# untitled.net
KiCad netlist of a schematic drawn in EAGLE
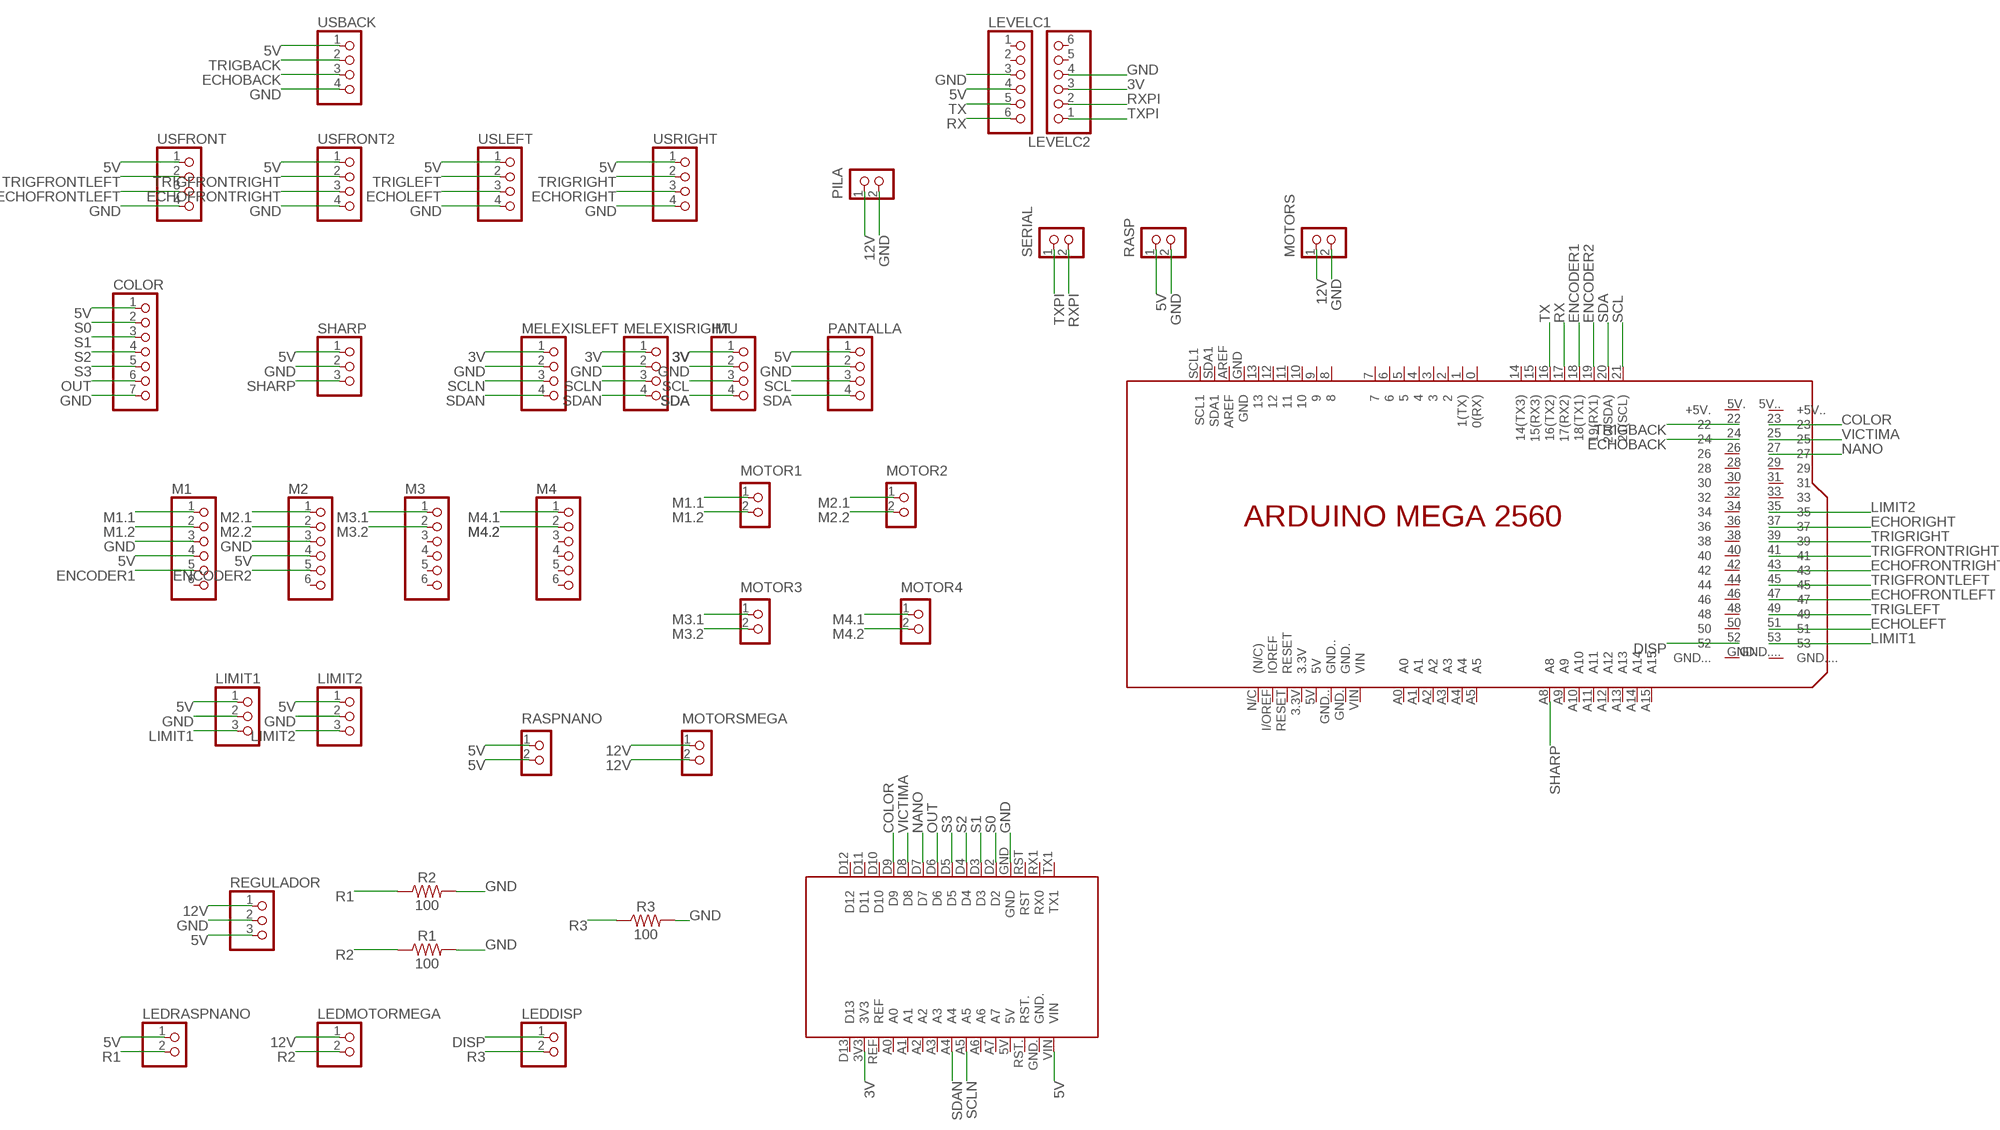
[diagram p0: schematic, sheet 1]

(export (version "E")
  (design (tool "Eeschema 10.0.6"))
  (components
    (comp (ref "COLOR")
      (value "PINHD-1X7")
      (footprint "eagle-import:1X07")
      (libsource (lib "eagle-import") (part "PINHD-1X7"))
    )
    (comp (ref "IMU")
      (value "PINHD-1X4")
      (footprint "eagle-import:1X04")
      (libsource (lib "eagle-import") (part "PINHD-1X4"))
    )
    (comp (ref "LEDDISP")
      (value "PINHD-1X2")
      (footprint "eagle-import:1X02")
      (libsource (lib "eagle-import") (part "PINHD-1X2"))
    )
    (comp (ref "LEDMOTORMEGA")
      (value "PINHD-1X2")
      (footprint "eagle-import:1X02")
      (libsource (lib "eagle-import") (part "PINHD-1X2"))
    )
    (comp (ref "LEDRASPNANO")
      (value "PINHD-1X2")
      (footprint "eagle-import:1X02")
      (libsource (lib "eagle-import") (part "PINHD-1X2"))
    )
    (comp (ref "LEVELC1")
      (value "PINHD-1X6")
      (footprint "eagle-import:1X06")
      (libsource (lib "eagle-import") (part "PINHD-1X6"))
    )
    (comp (ref "LEVELC2")
      (value "PINHD-1X6")
      (footprint "eagle-import:1X06")
      (libsource (lib "eagle-import") (part "PINHD-1X6"))
    )
    (comp (ref "LIMIT1")
      (value "PINHD-1X3")
      (footprint "eagle-import:1X03")
      (libsource (lib "eagle-import") (part "PINHD-1X3"))
    )
    (comp (ref "LIMIT2")
      (value "PINHD-1X3")
      (footprint "eagle-import:1X03")
      (libsource (lib "eagle-import") (part "PINHD-1X3"))
    )
    (comp (ref "M1")
      (value "PINHD-1X6")
      (footprint "eagle-import:1X06")
      (libsource (lib "eagle-import") (part "PINHD-1X6"))
    )
    (comp (ref "M2")
      (value "PINHD-1X6")
      (footprint "eagle-import:1X06")
      (libsource (lib "eagle-import") (part "PINHD-1X6"))
    )
    (comp (ref "M3")
      (value "PINHD-1X6")
      (footprint "eagle-import:1X06")
      (libsource (lib "eagle-import") (part "PINHD-1X6"))
    )
    (comp (ref "M4")
      (value "PINHD-1X6")
      (footprint "eagle-import:1X06")
      (libsource (lib "eagle-import") (part "PINHD-1X6"))
    )
    (comp (ref "MEGA1")
      (value "MEGA")
      (footprint "eagle-import:MEGA")
      (libsource (lib "eagle-import") (part "MEGA"))
    )
    (comp (ref "MELEXISLEFT")
      (value "PINHD-1X4")
      (footprint "eagle-import:1X04")
      (libsource (lib "eagle-import") (part "PINHD-1X4"))
    )
    (comp (ref "MELEXISRIGHT")
      (value "PINHD-1X4")
      (footprint "eagle-import:1X04")
      (libsource (lib "eagle-import") (part "PINHD-1X4"))
    )
    (comp (ref "MOTOR1")
      (value "CON_TERMINAL_BLOCK_02-5MM")
      (footprint "eagle-import:TERMINAL_BLOCK_2P_5")
      (libsource (lib "eagle-import") (part "CON_TERMINAL_BLOCK_02-5MM"))
    )
    (comp (ref "MOTOR2")
      (value "CON_TERMINAL_BLOCK_02-5MM")
      (footprint "eagle-import:TERMINAL_BLOCK_2P_5")
      (libsource (lib "eagle-import") (part "CON_TERMINAL_BLOCK_02-5MM"))
    )
    (comp (ref "MOTOR3")
      (value "CON_TERMINAL_BLOCK_02-5MM")
      (footprint "eagle-import:TERMINAL_BLOCK_2P_5")
      (libsource (lib "eagle-import") (part "CON_TERMINAL_BLOCK_02-5MM"))
    )
    (comp (ref "MOTOR4")
      (value "CON_TERMINAL_BLOCK_02-5MM")
      (footprint "eagle-import:TERMINAL_BLOCK_2P_5")
      (libsource (lib "eagle-import") (part "CON_TERMINAL_BLOCK_02-5MM"))
    )
    (comp (ref "MOTORS")
      (value "CON_TERMINAL_BLOCK_02-5MM")
      (footprint "eagle-import:TERMINAL_BLOCK_2P_5")
      (libsource (lib "eagle-import") (part "CON_TERMINAL_BLOCK_02-5MM"))
    )
    (comp (ref "MOTORSMEGA")
      (value "CON_TERMINAL_BLOCK_02-5MM")
      (footprint "eagle-import:TERMINAL_BLOCK_2P_5")
      (libsource (lib "eagle-import") (part "CON_TERMINAL_BLOCK_02-5MM"))
    )
    (comp (ref "PANTALLA")
      (value "PINHD-1X4")
      (footprint "eagle-import:1X04")
      (libsource (lib "eagle-import") (part "PINHD-1X4"))
    )
    (comp (ref "PILA")
      (value "CON_TERMINAL_BLOCK_02-5MM")
      (footprint "eagle-import:TERMINAL_BLOCK_2P_5")
      (libsource (lib "eagle-import") (part "CON_TERMINAL_BLOCK_02-5MM"))
    )
    (comp (ref "R1")
      (value "100")
      (footprint "eagle-import:AXIAL-0.3EZ")
      (libsource (lib "eagle-import") (part "100OHM-HORIZ_KIT-1/4W-1%"))
    )
    (comp (ref "R2")
      (value "100")
      (footprint "eagle-import:AXIAL-0.3EZ")
      (libsource (lib "eagle-import") (part "100OHM-HORIZ_KIT-1/4W-1%"))
    )
    (comp (ref "R3")
      (value "100")
      (footprint "eagle-import:AXIAL-0.3EZ")
      (libsource (lib "eagle-import") (part "100OHM-HORIZ_KIT-1/4W-1%"))
    )
    (comp (ref "RASP")
      (value "CON_TERMINAL_BLOCK_02-5MM")
      (footprint "eagle-import:TERMINAL_BLOCK_2P_5")
      (libsource (lib "eagle-import") (part "CON_TERMINAL_BLOCK_02-5MM"))
    )
    (comp (ref "RASPNANO")
      (value "CON_TERMINAL_BLOCK_02-5MM")
      (footprint "eagle-import:TERMINAL_BLOCK_2P_5")
      (libsource (lib "eagle-import") (part "CON_TERMINAL_BLOCK_02-5MM"))
    )
    (comp (ref "REGULADOR")
      (value "PINHD-1X3")
      (footprint "eagle-import:1X03")
      (libsource (lib "eagle-import") (part "PINHD-1X3"))
    )
    (comp (ref "SERIAL")
      (value "CON_TERMINAL_BLOCK_02-5MM")
      (footprint "eagle-import:TERMINAL_BLOCK_2P_5")
      (libsource (lib "eagle-import") (part "CON_TERMINAL_BLOCK_02-5MM"))
    )
    (comp (ref "SHARP")
      (value "PINHD-1X3")
      (footprint "eagle-import:1X03")
      (libsource (lib "eagle-import") (part "PINHD-1X3"))
    )
    (comp (ref "U$1")
      (value "NANO")
      (footprint "eagle-import:NANO")
      (libsource (lib "eagle-import") (part "NANO"))
    )
    (comp (ref "USBACK")
      (value "PINHD-1X4")
      (footprint "eagle-import:1X04")
      (libsource (lib "eagle-import") (part "PINHD-1X4"))
    )
    (comp (ref "USFRONT")
      (value "PINHD-1X4")
      (footprint "eagle-import:1X04")
      (libsource (lib "eagle-import") (part "PINHD-1X4"))
    )
    (comp (ref "USFRONT2")
      (value "PINHD-1X4")
      (footprint "eagle-import:1X04")
      (libsource (lib "eagle-import") (part "PINHD-1X4"))
    )
    (comp (ref "USLEFT")
      (value "PINHD-1X4")
      (footprint "eagle-import:1X04")
      (libsource (lib "eagle-import") (part "PINHD-1X4"))
    )
    (comp (ref "USRIGHT")
      (value "PINHD-1X4")
      (footprint "eagle-import:1X04")
      (libsource (lib "eagle-import") (part "PINHD-1X4"))
    )
  )
  (nets
    (net (code "1") (name "/3V") (class "Default")
      (node (ref "IMU") (pin "1") (pinfunction "1_1") (pintype "passive"))
      (node (ref "LEVELC2") (pin "3") (pinfunction "3_3") (pintype "passive"))
      (node (ref "MELEXISLEFT") (pin "1") (pinfunction "1_1") (pintype "passive"))
      (node (ref "MELEXISRIGHT") (pin "1") (pinfunction "1_1") (pintype "passive"))
      (node (ref "U$1") (pin "3V3") (pinfunction "3V3_3V3") (pintype "bidirectional"))
    )
    (net (code "2") (name "/5V") (class "Default")
      (node (ref "COLOR") (pin "1") (pinfunction "1_1") (pintype "passive"))
      (node (ref "LEDRASPNANO") (pin "1") (pinfunction "1_1") (pintype "passive"))
      (node (ref "LEVELC1") (pin "4") (pinfunction "4_4") (pintype "passive"))
      (node (ref "LIMIT1") (pin "1") (pinfunction "1_1") (pintype "passive"))
      (node (ref "LIMIT2") (pin "1") (pinfunction "1_1") (pintype "passive"))
      (node (ref "M1") (pin "4") (pinfunction "4_4") (pintype "passive"))
      (node (ref "M2") (pin "4") (pinfunction "4_4") (pintype "passive"))
      (node (ref "PANTALLA") (pin "1") (pinfunction "1_1") (pintype "passive"))
      (node (ref "RASP") (pin "1") (pinfunction "1_1") (pintype "passive"))
      (node (ref "RASPNANO") (pin "1") (pinfunction "1_1") (pintype "passive"))
      (node (ref "RASPNANO") (pin "2") (pinfunction "2_2") (pintype "passive"))
      (node (ref "REGULADOR") (pin "3") (pinfunction "3_3") (pintype "passive"))
      (node (ref "SHARP") (pin "1") (pinfunction "1_1") (pintype "passive"))
      (node (ref "U$1") (pin "VIN") (pinfunction "VIN_VIN") (pintype "bidirectional"))
      (node (ref "USBACK") (pin "1") (pinfunction "1_1") (pintype "passive"))
      (node (ref "USFRONT") (pin "1") (pinfunction "1_1") (pintype "passive"))
      (node (ref "USFRONT2") (pin "1") (pinfunction "1_1") (pintype "passive"))
      (node (ref "USLEFT") (pin "1") (pinfunction "1_1") (pintype "passive"))
      (node (ref "USRIGHT") (pin "1") (pinfunction "1_1") (pintype "passive"))
    )
    (net (code "3") (name "/12V") (class "Default")
      (node (ref "LEDMOTORMEGA") (pin "1") (pinfunction "1_1") (pintype "passive"))
      (node (ref "MOTORS") (pin "1") (pinfunction "1_1") (pintype "passive"))
      (node (ref "MOTORSMEGA") (pin "1") (pinfunction "1_1") (pintype "passive"))
      (node (ref "MOTORSMEGA") (pin "2") (pinfunction "2_2") (pintype "passive"))
      (node (ref "PILA") (pin "1") (pinfunction "1_1") (pintype "passive"))
      (node (ref "REGULADOR") (pin "1") (pinfunction "1_1") (pintype "passive"))
    )
    (net (code "4") (name "/COLOR") (class "Default")
      (node (ref "MEGA1") (pin "23") (pinfunction "23_23") (pintype "bidirectional"))
      (node (ref "U$1") (pin "D9") (pinfunction "D9_D9") (pintype "bidirectional"))
    )
    (net (code "5") (name "/DISP") (class "Default")
      (node (ref "LEDDISP") (pin "1") (pinfunction "1_1") (pintype "passive"))
      (node (ref "MEGA1") (pin "52") (pinfunction "52_52") (pintype "bidirectional"))
    )
    (net (code "6") (name "/ECHOBACK") (class "Default")
      (node (ref "MEGA1") (pin "24") (pinfunction "24_24") (pintype "bidirectional"))
      (node (ref "USBACK") (pin "3") (pinfunction "3_3") (pintype "passive"))
    )
    (net (code "7") (name "/ECHOFRONTLEFT") (class "Default")
      (node (ref "MEGA1") (pin "47") (pinfunction "47_47") (pintype "bidirectional"))
      (node (ref "USFRONT") (pin "3") (pinfunction "3_3") (pintype "passive"))
    )
    (net (code "8") (name "/ECHOFRONTRIGHT") (class "Default")
      (node (ref "MEGA1") (pin "43") (pinfunction "43_43") (pintype "bidirectional"))
      (node (ref "USFRONT2") (pin "3") (pinfunction "3_3") (pintype "passive"))
    )
    (net (code "9") (name "/ECHOLEFT") (class "Default")
      (node (ref "MEGA1") (pin "51") (pinfunction "51_51") (pintype "bidirectional"))
      (node (ref "USLEFT") (pin "3") (pinfunction "3_3") (pintype "passive"))
    )
    (net (code "10") (name "/ECHORIGHT") (class "Default")
      (node (ref "MEGA1") (pin "37") (pinfunction "37_37") (pintype "bidirectional"))
      (node (ref "USRIGHT") (pin "3") (pinfunction "3_3") (pintype "passive"))
    )
    (net (code "11") (name "/ENCODER1") (class "Default")
      (node (ref "M1") (pin "5") (pinfunction "5_5") (pintype "passive"))
      (node (ref "MEGA1") (pin "18") (pinfunction "18(TX1)_18") (pintype "bidirectional"))
    )
    (net (code "12") (name "/ENCODER2") (class "Default")
      (node (ref "M2") (pin "5") (pinfunction "5_5") (pintype "passive"))
      (node (ref "MEGA1") (pin "19") (pinfunction "19(RX1)_19") (pintype "bidirectional"))
    )
    (net (code "13") (name "/GND") (class "Default")
      (node (ref "COLOR") (pin "7") (pinfunction "7_7") (pintype "passive"))
      (node (ref "IMU") (pin "2") (pinfunction "2_2") (pintype "passive"))
      (node (ref "LEVELC1") (pin "3") (pinfunction "3_3") (pintype "passive"))
      (node (ref "LEVELC2") (pin "4") (pinfunction "4_4") (pintype "passive"))
      (node (ref "LIMIT1") (pin "2") (pinfunction "2_2") (pintype "passive"))
      (node (ref "LIMIT2") (pin "2") (pinfunction "2_2") (pintype "passive"))
      (node (ref "M1") (pin "3") (pinfunction "3_3") (pintype "passive"))
      (node (ref "M2") (pin "3") (pinfunction "3_3") (pintype "passive"))
      (node (ref "MELEXISLEFT") (pin "2") (pinfunction "2_2") (pintype "passive"))
      (node (ref "MELEXISRIGHT") (pin "2") (pinfunction "2_2") (pintype "passive"))
      (node (ref "MOTORS") (pin "2") (pinfunction "2_2") (pintype "passive"))
      (node (ref "PANTALLA") (pin "2") (pinfunction "2_2") (pintype "passive"))
      (node (ref "PILA") (pin "2") (pinfunction "2_2") (pintype "passive"))
      (node (ref "R1") (pin "P$2") (pinfunction "2_P$2") (pintype "passive"))
      (node (ref "R2") (pin "P$2") (pinfunction "2_P$2") (pintype "passive"))
      (node (ref "R3") (pin "P$2") (pinfunction "2_P$2") (pintype "passive"))
      (node (ref "RASP") (pin "2") (pinfunction "2_2") (pintype "passive"))
      (node (ref "REGULADOR") (pin "2") (pinfunction "2_2") (pintype "passive"))
      (node (ref "SHARP") (pin "2") (pinfunction "2_2") (pintype "passive"))
      (node (ref "U$1") (pin "GND") (pinfunction "GND_GND") (pintype "bidirectional"))
      (node (ref "USBACK") (pin "4") (pinfunction "4_4") (pintype "passive"))
      (node (ref "USFRONT") (pin "4") (pinfunction "4_4") (pintype "passive"))
      (node (ref "USFRONT2") (pin "4") (pinfunction "4_4") (pintype "passive"))
      (node (ref "USLEFT") (pin "4") (pinfunction "4_4") (pintype "passive"))
      (node (ref "USRIGHT") (pin "4") (pinfunction "4_4") (pintype "passive"))
    )
    (net (code "14") (name "/LIMIT1") (class "Default")
      (node (ref "LIMIT1") (pin "3") (pinfunction "3_3") (pintype "passive"))
      (node (ref "MEGA1") (pin "53") (pinfunction "53_53") (pintype "bidirectional"))
    )
    (net (code "15") (name "/LIMIT2") (class "Default")
      (node (ref "LIMIT2") (pin "3") (pinfunction "3_3") (pintype "passive"))
      (node (ref "MEGA1") (pin "35") (pinfunction "35_35") (pintype "bidirectional"))
    )
    (net (code "16") (name "/M1.1") (class "Default")
      (node (ref "M1") (pin "1") (pinfunction "1_1") (pintype "passive"))
      (node (ref "MOTOR1") (pin "1") (pinfunction "1_1") (pintype "passive"))
    )
    (net (code "17") (name "/M1.2") (class "Default")
      (node (ref "M1") (pin "2") (pinfunction "2_2") (pintype "passive"))
      (node (ref "MOTOR1") (pin "2") (pinfunction "2_2") (pintype "passive"))
    )
    (net (code "18") (name "/M2.1") (class "Default")
      (node (ref "M2") (pin "1") (pinfunction "1_1") (pintype "passive"))
      (node (ref "MOTOR2") (pin "1") (pinfunction "1_1") (pintype "passive"))
    )
    (net (code "19") (name "/M2.2") (class "Default")
      (node (ref "M2") (pin "2") (pinfunction "2_2") (pintype "passive"))
      (node (ref "MOTOR2") (pin "2") (pinfunction "2_2") (pintype "passive"))
    )
    (net (code "20") (name "/M3.1") (class "Default")
      (node (ref "M3") (pin "1") (pinfunction "1_1") (pintype "passive"))
      (node (ref "MOTOR3") (pin "1") (pinfunction "1_1") (pintype "passive"))
    )
    (net (code "21") (name "/M3.2") (class "Default")
      (node (ref "M3") (pin "2") (pinfunction "2_2") (pintype "passive"))
      (node (ref "MOTOR3") (pin "2") (pinfunction "2_2") (pintype "passive"))
    )
    (net (code "22") (name "/M4.1") (class "Default")
      (node (ref "M4") (pin "1") (pinfunction "1_1") (pintype "passive"))
      (node (ref "MOTOR4") (pin "1") (pinfunction "1_1") (pintype "passive"))
    )
    (net (code "23") (name "/M4.2") (class "Default")
      (node (ref "M4") (pin "2") (pinfunction "2_2") (pintype "passive"))
      (node (ref "MOTOR4") (pin "2") (pinfunction "2_2") (pintype "passive"))
    )
    (net (code "24") (name "/NANO") (class "Default")
      (node (ref "MEGA1") (pin "27") (pinfunction "27_27") (pintype "bidirectional"))
      (node (ref "U$1") (pin "D7") (pinfunction "D7_D7") (pintype "bidirectional"))
    )
    (net (code "25") (name "/OUT") (class "Default")
      (node (ref "COLOR") (pin "6") (pinfunction "6_6") (pintype "passive"))
      (node (ref "U$1") (pin "D6") (pinfunction "D6_D6") (pintype "bidirectional"))
    )
    (net (code "26") (name "/R1") (class "Default")
      (node (ref "LEDRASPNANO") (pin "2") (pinfunction "2_2") (pintype "passive"))
      (node (ref "R2") (pin "P$1") (pinfunction "1_P$1") (pintype "passive"))
    )
    (net (code "27") (name "/R2") (class "Default")
      (node (ref "LEDMOTORMEGA") (pin "2") (pinfunction "2_2") (pintype "passive"))
      (node (ref "R1") (pin "P$1") (pinfunction "1_P$1") (pintype "passive"))
    )
    (net (code "28") (name "/R3") (class "Default")
      (node (ref "LEDDISP") (pin "2") (pinfunction "2_2") (pintype "passive"))
      (node (ref "R3") (pin "P$1") (pinfunction "1_P$1") (pintype "passive"))
    )
    (net (code "29") (name "/RX") (class "Default")
      (node (ref "LEVELC1") (pin "6") (pinfunction "6_6") (pintype "passive"))
      (node (ref "MEGA1") (pin "17") (pinfunction "17(RX2)_17") (pintype "bidirectional"))
    )
    (net (code "30") (name "/RXPI") (class "Default")
      (node (ref "LEVELC2") (pin "2") (pinfunction "2_2") (pintype "passive"))
      (node (ref "SERIAL") (pin "2") (pinfunction "2_2") (pintype "passive"))
    )
    (net (code "31") (name "/S0") (class "Default")
      (node (ref "COLOR") (pin "2") (pinfunction "2_2") (pintype "passive"))
      (node (ref "U$1") (pin "D2") (pinfunction "D2_D2") (pintype "bidirectional"))
    )
    (net (code "32") (name "/S1") (class "Default")
      (node (ref "COLOR") (pin "3") (pinfunction "3_3") (pintype "passive"))
      (node (ref "U$1") (pin "D3") (pinfunction "D3_D3") (pintype "bidirectional"))
    )
    (net (code "33") (name "/S2") (class "Default")
      (node (ref "COLOR") (pin "4") (pinfunction "4_4") (pintype "passive"))
      (node (ref "U$1") (pin "D4") (pinfunction "D4_D4") (pintype "bidirectional"))
    )
    (net (code "34") (name "/S3") (class "Default")
      (node (ref "COLOR") (pin "5") (pinfunction "5_5") (pintype "passive"))
      (node (ref "U$1") (pin "D5") (pinfunction "D5_D5") (pintype "bidirectional"))
    )
    (net (code "35") (name "/SCL") (class "Default")
      (node (ref "IMU") (pin "3") (pinfunction "3_3") (pintype "passive"))
      (node (ref "MEGA1") (pin "21") (pinfunction "21(SCL)_21") (pintype "bidirectional"))
      (node (ref "PANTALLA") (pin "3") (pinfunction "3_3") (pintype "passive"))
    )
    (net (code "36") (name "/SCLN") (class "Default")
      (node (ref "MELEXISLEFT") (pin "3") (pinfunction "3_3") (pintype "passive"))
      (node (ref "MELEXISRIGHT") (pin "3") (pinfunction "3_3") (pintype "passive"))
      (node (ref "U$1") (pin "A5") (pinfunction "A5_A5") (pintype "bidirectional"))
    )
    (net (code "37") (name "/SDA") (class "Default")
      (node (ref "IMU") (pin "4") (pinfunction "4_4") (pintype "passive"))
      (node (ref "MEGA1") (pin "20") (pinfunction "20(SDA)_20") (pintype "bidirectional"))
      (node (ref "PANTALLA") (pin "4") (pinfunction "4_4") (pintype "passive"))
    )
    (net (code "38") (name "/SDAN") (class "Default")
      (node (ref "MELEXISLEFT") (pin "4") (pinfunction "4_4") (pintype "passive"))
      (node (ref "MELEXISRIGHT") (pin "4") (pinfunction "4_4") (pintype "passive"))
      (node (ref "U$1") (pin "A4") (pinfunction "A4_A4") (pintype "bidirectional"))
    )
    (net (code "39") (name "/SHARP") (class "Default")
      (node (ref "MEGA1") (pin "A8") (pinfunction "A8_A8") (pintype "bidirectional"))
      (node (ref "SHARP") (pin "3") (pinfunction "3_3") (pintype "passive"))
    )
    (net (code "40") (name "/TRIGBACK") (class "Default")
      (node (ref "MEGA1") (pin "22") (pinfunction "22_22") (pintype "bidirectional"))
      (node (ref "USBACK") (pin "2") (pinfunction "2_2") (pintype "passive"))
    )
    (net (code "41") (name "/TRIGFRONTLEFT") (class "Default")
      (node (ref "MEGA1") (pin "45") (pinfunction "45_45") (pintype "bidirectional"))
      (node (ref "USFRONT") (pin "2") (pinfunction "2_2") (pintype "passive"))
    )
    (net (code "42") (name "/TRIGFRONTRIGHT") (class "Default")
      (node (ref "MEGA1") (pin "41") (pinfunction "41_41") (pintype "bidirectional"))
      (node (ref "USFRONT2") (pin "2") (pinfunction "2_2") (pintype "passive"))
    )
    (net (code "43") (name "/TRIGLEFT") (class "Default")
      (node (ref "MEGA1") (pin "49") (pinfunction "49_49") (pintype "bidirectional"))
      (node (ref "USLEFT") (pin "2") (pinfunction "2_2") (pintype "passive"))
    )
    (net (code "44") (name "/TRIGRIGHT") (class "Default")
      (node (ref "MEGA1") (pin "39") (pinfunction "39_39") (pintype "bidirectional"))
      (node (ref "USRIGHT") (pin "2") (pinfunction "2_2") (pintype "passive"))
    )
    (net (code "45") (name "/TX") (class "Default")
      (node (ref "LEVELC1") (pin "5") (pinfunction "5_5") (pintype "passive"))
      (node (ref "MEGA1") (pin "16") (pinfunction "16(TX2)_16") (pintype "bidirectional"))
    )
    (net (code "46") (name "/TXPI") (class "Default")
      (node (ref "LEVELC2") (pin "1") (pinfunction "1_1") (pintype "passive"))
      (node (ref "SERIAL") (pin "1") (pinfunction "1_1") (pintype "passive"))
    )
    (net (code "47") (name "/VICTIMA") (class "Default")
      (node (ref "MEGA1") (pin "25") (pinfunction "25_25") (pintype "bidirectional"))
      (node (ref "U$1") (pin "D8") (pinfunction "D8_D8") (pintype "bidirectional"))
    )
    (net (code "48") (name "unconnected-(LEVELC1-Pad1)") (class "Default")
      (node (ref "LEVELC1") (pin "1") (pinfunction "1_1") (pintype "passive"))
    )
    (net (code "49") (name "unconnected-(LEVELC1-Pad2)") (class "Default")
      (node (ref "LEVELC1") (pin "2") (pinfunction "2_2") (pintype "passive"))
    )
    (net (code "50") (name "unconnected-(LEVELC2-Pad5)") (class "Default")
      (node (ref "LEVELC2") (pin "5") (pinfunction "5_5") (pintype "passive"))
    )
    (net (code "51") (name "unconnected-(LEVELC2-Pad6)") (class "Default")
      (node (ref "LEVELC2") (pin "6") (pinfunction "6_6") (pintype "passive"))
    )
    (net (code "52") (name "unconnected-(M1-Pad6)") (class "Default")
      (node (ref "M1") (pin "6") (pinfunction "6_6") (pintype "passive"))
    )
    (net (code "53") (name "unconnected-(M2-Pad6)") (class "Default")
      (node (ref "M2") (pin "6") (pinfunction "6_6") (pintype "passive"))
    )
    (net (code "54") (name "unconnected-(M3-Pad3)") (class "Default")
      (node (ref "M3") (pin "3") (pinfunction "3_3") (pintype "passive"))
    )
    (net (code "55") (name "unconnected-(M3-Pad4)") (class "Default")
      (node (ref "M3") (pin "4") (pinfunction "4_4") (pintype "passive"))
    )
    (net (code "56") (name "unconnected-(M3-Pad5)") (class "Default")
      (node (ref "M3") (pin "5") (pinfunction "5_5") (pintype "passive"))
    )
    (net (code "57") (name "unconnected-(M3-Pad6)") (class "Default")
      (node (ref "M3") (pin "6") (pinfunction "6_6") (pintype "passive"))
    )
    (net (code "58") (name "unconnected-(M4-Pad3)") (class "Default")
      (node (ref "M4") (pin "3") (pinfunction "3_3") (pintype "passive"))
    )
    (net (code "59") (name "unconnected-(M4-Pad4)") (class "Default")
      (node (ref "M4") (pin "4") (pinfunction "4_4") (pintype "passive"))
    )
    (net (code "60") (name "unconnected-(M4-Pad5)") (class "Default")
      (node (ref "M4") (pin "5") (pinfunction "5_5") (pintype "passive"))
    )
    (net (code "61") (name "unconnected-(M4-Pad6)") (class "Default")
      (node (ref "M4") (pin "6") (pinfunction "6_6") (pintype "passive"))
    )
    (net (code "62") (name "unconnected-(MEGA1-(N{slash}C)-PadN{slash}C)") (class "Default")
      (node (ref "MEGA1") (pin "N/C") (pinfunction "(N/C)_N/C") (pintype "bidirectional"))
    )
    (net (code "63") (name "unconnected-(MEGA1-+5V.-Pad5V.)") (class "Default")
      (node (ref "MEGA1") (pin "5V.") (pinfunction "+5V._5V.") (pintype "bidirectional"))
    )
    (net (code "64") (name "unconnected-(MEGA1-+5V..-Pad5V..)") (class "Default")
      (node (ref "MEGA1") (pin "5V..") (pinfunction "+5V.._5V..") (pintype "bidirectional"))
    )
    (net (code "65") (name "unconnected-(MEGA1-0(RX)-Pad0)") (class "Default")
      (node (ref "MEGA1") (pin "0") (pinfunction "0(RX)_0") (pintype "bidirectional"))
    )
    (net (code "66") (name "unconnected-(MEGA1-1(TX)-Pad1)") (class "Default")
      (node (ref "MEGA1") (pin "1") (pinfunction "1(TX)_1") (pintype "bidirectional"))
    )
    (net (code "67") (name "unconnected-(MEGA1-14(TX3)-Pad14)") (class "Default")
      (node (ref "MEGA1") (pin "14") (pinfunction "14(TX3)_14") (pintype "bidirectional"))
    )
    (net (code "68") (name "unconnected-(MEGA1-15(RX3)-Pad15)") (class "Default")
      (node (ref "MEGA1") (pin "15") (pinfunction "15(RX3)_15") (pintype "bidirectional"))
    )
    (net (code "69") (name "unconnected-(MEGA1-IOREF-PadI{slash}OREF)") (class "Default")
      (node (ref "MEGA1") (pin "I/OREF") (pinfunction "IOREF_I/OREF") (pintype "bidirectional"))
    )
    (net (code "70") (name "unconnected-(MEGA1-Pad2)") (class "Default")
      (node (ref "MEGA1") (pin "2") (pinfunction "2_2") (pintype "bidirectional"))
    )
    (net (code "71") (name "unconnected-(MEGA1-Pad3)") (class "Default")
      (node (ref "MEGA1") (pin "3") (pinfunction "3_3") (pintype "bidirectional"))
    )
    (net (code "72") (name "unconnected-(MEGA1-Pad3.3V)") (class "Default")
      (node (ref "MEGA1") (pin "3.3V") (pinfunction "3.3V_3.3V") (pintype "bidirectional"))
    )
    (net (code "73") (name "unconnected-(MEGA1-Pad4)") (class "Default")
      (node (ref "MEGA1") (pin "4") (pinfunction "4_4") (pintype "bidirectional"))
    )
    (net (code "74") (name "unconnected-(MEGA1-Pad5)") (class "Default")
      (node (ref "MEGA1") (pin "5") (pinfunction "5_5") (pintype "bidirectional"))
    )
    (net (code "75") (name "unconnected-(MEGA1-Pad5V)") (class "Default")
      (node (ref "MEGA1") (pin "5V") (pinfunction "5V_5V") (pintype "bidirectional"))
    )
    (net (code "76") (name "unconnected-(MEGA1-Pad6)") (class "Default")
      (node (ref "MEGA1") (pin "6") (pinfunction "6_6") (pintype "bidirectional"))
    )
    (net (code "77") (name "unconnected-(MEGA1-Pad7)") (class "Default")
      (node (ref "MEGA1") (pin "7") (pinfunction "7_7") (pintype "bidirectional"))
    )
    (net (code "78") (name "unconnected-(MEGA1-Pad8)") (class "Default")
      (node (ref "MEGA1") (pin "8") (pinfunction "8_8") (pintype "bidirectional"))
    )
    (net (code "79") (name "unconnected-(MEGA1-Pad9)") (class "Default")
      (node (ref "MEGA1") (pin "9") (pinfunction "9_9") (pintype "bidirectional"))
    )
    (net (code "80") (name "unconnected-(MEGA1-Pad10)") (class "Default")
      (node (ref "MEGA1") (pin "10") (pinfunction "10_10") (pintype "bidirectional"))
    )
    (net (code "81") (name "unconnected-(MEGA1-Pad11)") (class "Default")
      (node (ref "MEGA1") (pin "11") (pinfunction "11_11") (pintype "bidirectional"))
    )
    (net (code "82") (name "unconnected-(MEGA1-Pad12)") (class "Default")
      (node (ref "MEGA1") (pin "12") (pinfunction "12_12") (pintype "bidirectional"))
    )
    (net (code "83") (name "unconnected-(MEGA1-Pad13)") (class "Default")
      (node (ref "MEGA1") (pin "13") (pinfunction "13_13") (pintype "bidirectional"))
    )
    (net (code "84") (name "unconnected-(MEGA1-Pad26)") (class "Default")
      (node (ref "MEGA1") (pin "26") (pinfunction "26_26") (pintype "bidirectional"))
    )
    (net (code "85") (name "unconnected-(MEGA1-Pad28)") (class "Default")
      (node (ref "MEGA1") (pin "28") (pinfunction "28_28") (pintype "bidirectional"))
    )
    (net (code "86") (name "unconnected-(MEGA1-Pad29)") (class "Default")
      (node (ref "MEGA1") (pin "29") (pinfunction "29_29") (pintype "bidirectional"))
    )
    (net (code "87") (name "unconnected-(MEGA1-Pad30)") (class "Default")
      (node (ref "MEGA1") (pin "30") (pinfunction "30_30") (pintype "bidirectional"))
    )
    (net (code "88") (name "unconnected-(MEGA1-Pad31)") (class "Default")
      (node (ref "MEGA1") (pin "31") (pinfunction "31_31") (pintype "bidirectional"))
    )
    (net (code "89") (name "unconnected-(MEGA1-Pad32)") (class "Default")
      (node (ref "MEGA1") (pin "32") (pinfunction "32_32") (pintype "bidirectional"))
    )
    (net (code "90") (name "unconnected-(MEGA1-Pad33)") (class "Default")
      (node (ref "MEGA1") (pin "33") (pinfunction "33_33") (pintype "bidirectional"))
    )
    (net (code "91") (name "unconnected-(MEGA1-Pad34)") (class "Default")
      (node (ref "MEGA1") (pin "34") (pinfunction "34_34") (pintype "bidirectional"))
    )
    (net (code "92") (name "unconnected-(MEGA1-Pad36)") (class "Default")
      (node (ref "MEGA1") (pin "36") (pinfunction "36_36") (pintype "bidirectional"))
    )
    (net (code "93") (name "unconnected-(MEGA1-Pad38)") (class "Default")
      (node (ref "MEGA1") (pin "38") (pinfunction "38_38") (pintype "bidirectional"))
    )
    (net (code "94") (name "unconnected-(MEGA1-Pad40)") (class "Default")
      (node (ref "MEGA1") (pin "40") (pinfunction "40_40") (pintype "bidirectional"))
    )
    (net (code "95") (name "unconnected-(MEGA1-Pad42)") (class "Default")
      (node (ref "MEGA1") (pin "42") (pinfunction "42_42") (pintype "bidirectional"))
    )
    (net (code "96") (name "unconnected-(MEGA1-Pad44)") (class "Default")
      (node (ref "MEGA1") (pin "44") (pinfunction "44_44") (pintype "bidirectional"))
    )
    (net (code "97") (name "unconnected-(MEGA1-Pad46)") (class "Default")
      (node (ref "MEGA1") (pin "46") (pinfunction "46_46") (pintype "bidirectional"))
    )
    (net (code "98") (name "unconnected-(MEGA1-Pad48)") (class "Default")
      (node (ref "MEGA1") (pin "48") (pinfunction "48_48") (pintype "bidirectional"))
    )
    (net (code "99") (name "unconnected-(MEGA1-Pad50)") (class "Default")
      (node (ref "MEGA1") (pin "50") (pinfunction "50_50") (pintype "bidirectional"))
    )
    (net (code "100") (name "unconnected-(MEGA1-PadA0)") (class "Default")
      (node (ref "MEGA1") (pin "A0") (pinfunction "A0_A0") (pintype "bidirectional"))
    )
    (net (code "101") (name "unconnected-(MEGA1-PadA1)") (class "Default")
      (node (ref "MEGA1") (pin "A1") (pinfunction "A1_A1") (pintype "bidirectional"))
    )
    (net (code "102") (name "unconnected-(MEGA1-PadA2)") (class "Default")
      (node (ref "MEGA1") (pin "A2") (pinfunction "A2_A2") (pintype "bidirectional"))
    )
    (net (code "103") (name "unconnected-(MEGA1-PadA3)") (class "Default")
      (node (ref "MEGA1") (pin "A3") (pinfunction "A3_A3") (pintype "bidirectional"))
    )
    (net (code "104") (name "unconnected-(MEGA1-PadA4)") (class "Default")
      (node (ref "MEGA1") (pin "A4") (pinfunction "A4_A4") (pintype "bidirectional"))
    )
    (net (code "105") (name "unconnected-(MEGA1-PadA5)") (class "Default")
      (node (ref "MEGA1") (pin "A5") (pinfunction "A5_A5") (pintype "bidirectional"))
    )
    (net (code "106") (name "unconnected-(MEGA1-PadA9)") (class "Default")
      (node (ref "MEGA1") (pin "A9") (pinfunction "A9_A9") (pintype "bidirectional"))
    )
    (net (code "107") (name "unconnected-(MEGA1-PadA10)") (class "Default")
      (node (ref "MEGA1") (pin "A10") (pinfunction "A10_A10") (pintype "bidirectional"))
    )
    (net (code "108") (name "unconnected-(MEGA1-PadA11)") (class "Default")
      (node (ref "MEGA1") (pin "A11") (pinfunction "A11_A11") (pintype "bidirectional"))
    )
    (net (code "109") (name "unconnected-(MEGA1-PadA12)") (class "Default")
      (node (ref "MEGA1") (pin "A12") (pinfunction "A12_A12") (pintype "bidirectional"))
    )
    (net (code "110") (name "unconnected-(MEGA1-PadA13)") (class "Default")
      (node (ref "MEGA1") (pin "A13") (pinfunction "A13_A13") (pintype "bidirectional"))
    )
    (net (code "111") (name "unconnected-(MEGA1-PadA14)") (class "Default")
      (node (ref "MEGA1") (pin "A14") (pinfunction "A14_A14") (pintype "bidirectional"))
    )
    (net (code "112") (name "unconnected-(MEGA1-PadA15)") (class "Default")
      (node (ref "MEGA1") (pin "A15") (pinfunction "A15_A15") (pintype "bidirectional"))
    )
    (net (code "113") (name "unconnected-(MEGA1-PadAREF)") (class "Default")
      (node (ref "MEGA1") (pin "AREF") (pinfunction "AREF_AREF") (pintype "bidirectional"))
    )
    (net (code "114") (name "unconnected-(MEGA1-PadGND)") (class "Default")
      (node (ref "MEGA1") (pin "GND") (pinfunction "GND_GND") (pintype "bidirectional"))
    )
    (net (code "115") (name "unconnected-(MEGA1-PadGND.)") (class "Default")
      (node (ref "MEGA1") (pin "GND.") (pinfunction "GND._GND.") (pintype "bidirectional"))
    )
    (net (code "116") (name "unconnected-(MEGA1-PadGND..)") (class "Default")
      (node (ref "MEGA1") (pin "GND..") (pinfunction "GND.._GND..") (pintype "bidirectional"))
    )
    (net (code "117") (name "unconnected-(MEGA1-PadGND...)") (class "Default")
      (node (ref "MEGA1") (pin "GND...") (pinfunction "GND..._GND...") (pintype "bidirectional"))
    )
    (net (code "118") (name "unconnected-(MEGA1-PadGND....)") (class "Default")
      (node (ref "MEGA1") (pin "GND....") (pinfunction "GND...._GND....") (pintype "bidirectional"))
    )
    (net (code "119") (name "unconnected-(MEGA1-PadRESET)") (class "Default")
      (node (ref "MEGA1") (pin "RESET") (pinfunction "RESET_RESET") (pintype "bidirectional"))
    )
    (net (code "120") (name "unconnected-(MEGA1-PadSCL1)") (class "Default")
      (node (ref "MEGA1") (pin "SCL1") (pinfunction "SCL1_SCL1") (pintype "bidirectional"))
    )
    (net (code "121") (name "unconnected-(MEGA1-PadSDA1)") (class "Default")
      (node (ref "MEGA1") (pin "SDA1") (pinfunction "SDA1_SDA1") (pintype "bidirectional"))
    )
    (net (code "122") (name "unconnected-(MEGA1-PadVIN)") (class "Default")
      (node (ref "MEGA1") (pin "VIN") (pinfunction "VIN_VIN") (pintype "bidirectional"))
    )
    (net (code "123") (name "unconnected-(U$1-Pad5V)") (class "Default")
      (node (ref "U$1") (pin "5V") (pinfunction "5V_5V") (pintype "bidirectional"))
    )
    (net (code "124") (name "unconnected-(U$1-PadA0)") (class "Default")
      (node (ref "U$1") (pin "A0") (pinfunction "A0_A0") (pintype "bidirectional"))
    )
    (net (code "125") (name "unconnected-(U$1-PadA1)") (class "Default")
      (node (ref "U$1") (pin "A1") (pinfunction "A1_A1") (pintype "bidirectional"))
    )
    (net (code "126") (name "unconnected-(U$1-PadA2)") (class "Default")
      (node (ref "U$1") (pin "A2") (pinfunction "A2_A2") (pintype "bidirectional"))
    )
    (net (code "127") (name "unconnected-(U$1-PadA3)") (class "Default")
      (node (ref "U$1") (pin "A3") (pinfunction "A3_A3") (pintype "bidirectional"))
    )
    (net (code "128") (name "unconnected-(U$1-PadA6)") (class "Default")
      (node (ref "U$1") (pin "A6") (pinfunction "A6_A6") (pintype "bidirectional"))
    )
    (net (code "129") (name "unconnected-(U$1-PadA7)") (class "Default")
      (node (ref "U$1") (pin "A7") (pinfunction "A7_A7") (pintype "bidirectional"))
    )
    (net (code "130") (name "unconnected-(U$1-PadD10)") (class "Default")
      (node (ref "U$1") (pin "D10") (pinfunction "D10_D10") (pintype "bidirectional"))
    )
    (net (code "131") (name "unconnected-(U$1-PadD11)") (class "Default")
      (node (ref "U$1") (pin "D11") (pinfunction "D11_D11") (pintype "bidirectional"))
    )
    (net (code "132") (name "unconnected-(U$1-PadD12)") (class "Default")
      (node (ref "U$1") (pin "D12") (pinfunction "D12_D12") (pintype "bidirectional"))
    )
    (net (code "133") (name "unconnected-(U$1-PadD13)") (class "Default")
      (node (ref "U$1") (pin "D13") (pinfunction "D13_D13") (pintype "bidirectional"))
    )
    (net (code "134") (name "unconnected-(U$1-PadGND.)") (class "Default")
      (node (ref "U$1") (pin "GND.") (pinfunction "GND._GND.") (pintype "bidirectional"))
    )
    (net (code "135") (name "unconnected-(U$1-PadREF)") (class "Default")
      (node (ref "U$1") (pin "REF") (pinfunction "REF_REF") (pintype "bidirectional"))
    )
    (net (code "136") (name "unconnected-(U$1-PadRST)") (class "Default")
      (node (ref "U$1") (pin "RST") (pinfunction "RST_RST") (pintype "bidirectional"))
    )
    (net (code "137") (name "unconnected-(U$1-PadRST.)") (class "Default")
      (node (ref "U$1") (pin "RST.") (pinfunction "RST._RST.") (pintype "bidirectional"))
    )
    (net (code "138") (name "unconnected-(U$1-PadTX1)") (class "Default")
      (node (ref "U$1") (pin "TX1") (pinfunction "TX1_TX1") (pintype "bidirectional"))
    )
    (net (code "139") (name "unconnected-(U$1-RX0-PadRX1)") (class "Default")
      (node (ref "U$1") (pin "RX1") (pinfunction "RX0_RX1") (pintype "bidirectional"))
    )
  )
)
